# XephConnect_v0_1.net
KiCad netlist of a schematic drawn in EAGLE
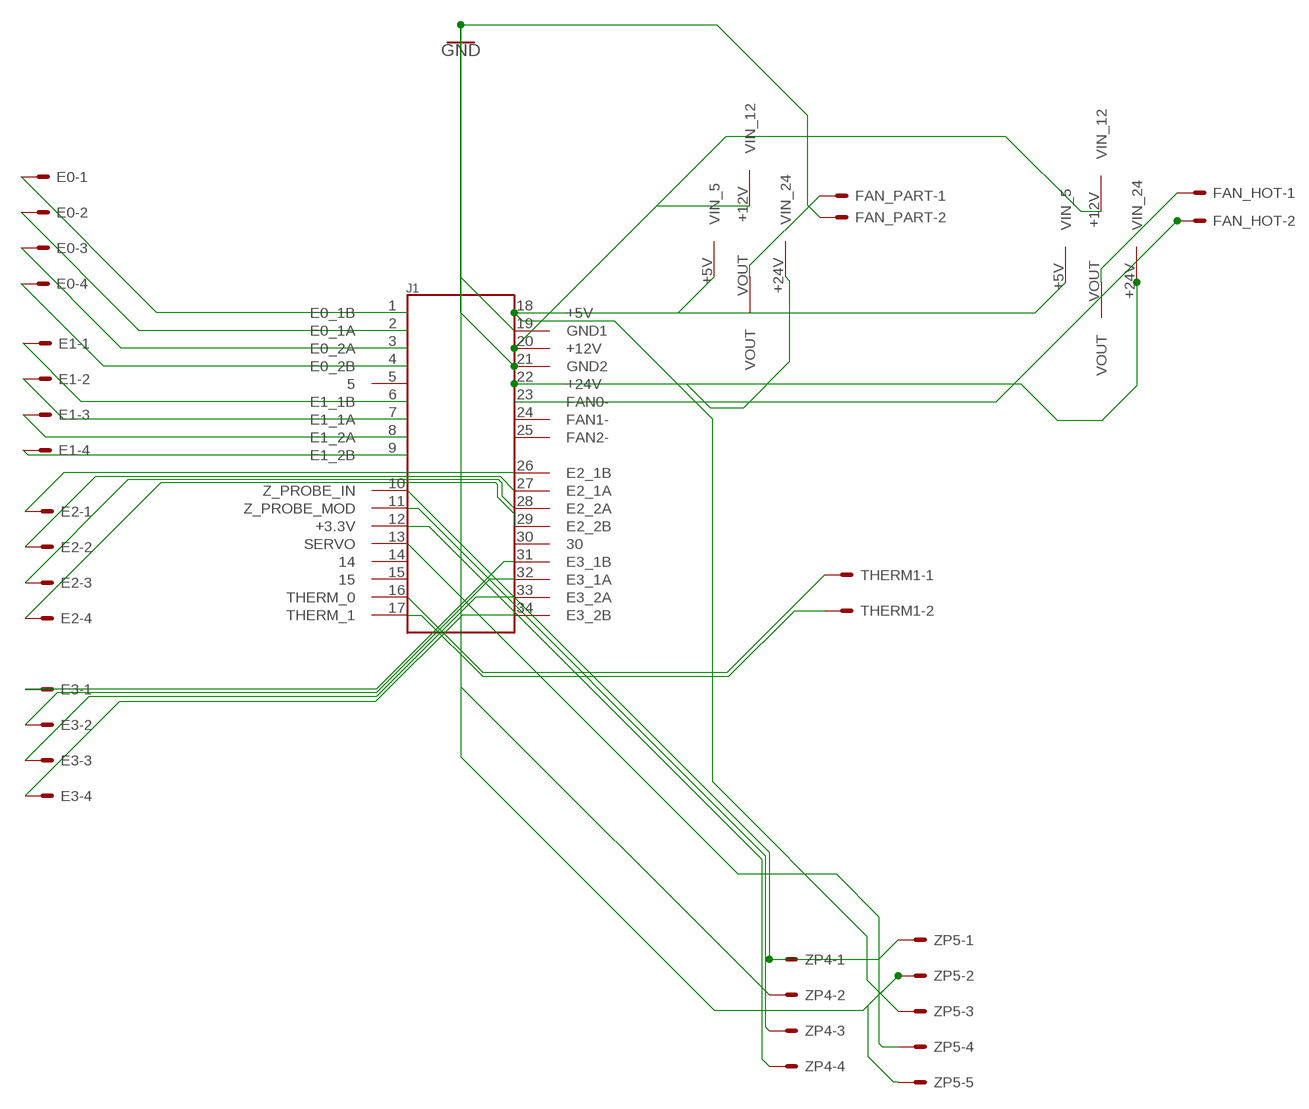
[diagram p0: schematic, sheet 1]

(export (version "E")
  (design (tool "Eeschema 10.0.6"))
  (components
    (comp (ref "E0")
      (value "22-27-2041-04")
      (footprint "eagle-import:6410-04")
      (fields (field (name "MF") "MOLEX"))
      (libsource (lib "eagle-import") (part "22-?-0427-2041"))
    )
    (comp (ref "E1")
      (value "22-27-2041-04")
      (footprint "eagle-import:6410-04")
      (fields (field (name "MF") "MOLEX"))
      (libsource (lib "eagle-import") (part "22-?-0427-2041"))
    )
    (comp (ref "E2")
      (value "22-27-2041-04")
      (footprint "eagle-import:6410-04")
      (fields (field (name "MF") "MOLEX"))
      (libsource (lib "eagle-import") (part "22-?-0427-2041"))
    )
    (comp (ref "E3")
      (value "22-27-2041-04")
      (footprint "eagle-import:6410-04")
      (fields (field (name "MF") "MOLEX"))
      (libsource (lib "eagle-import") (part "22-?-0427-2041"))
    )
    (comp (ref "FAN_HOT")
      (value "22-27-2021-02")
      (footprint "eagle-import:6410-02")
      (fields (field (name "MF") "MOLEX"))
      (libsource (lib "eagle-import") (part "22-?-0227-2021"))
    )
    (comp (ref "FAN_PART")
      (value "22-27-2021-02")
      (footprint "eagle-import:6410-02")
      (fields (field (name "MF") "MOLEX"))
      (libsource (lib "eagle-import") (part "22-?-0227-2021"))
    )
    (comp (ref "J1")
      (value "6437288-1")
      (footprint "eagle-import:TE_6437288-1")
      (fields (field (name "DIGI-KEY_PART_NUMBER") "A124384-ND") (field (name "MF") "TE Connectivity"))
      (libsource (lib "eagle-import") (part "6437288-1"))
    )
    (comp (ref "THERM1")
      (value "22-27-2021-02")
      (footprint "eagle-import:6410-02")
      (fields (field (name "MF") "MOLEX"))
      (libsource (lib "eagle-import") (part "22-?-0227-2021"))
    )
    (comp (ref "U$1")
      (value "CONN_03+01(T)")
      (footprint "eagle-import:1X03X01")
      (libsource (lib "eagle-import") (part "CONN_03+01(T)"))
    )
    (comp (ref "U$2")
      (value "CONN_03+01(T)")
      (footprint "eagle-import:1X03X01")
      (libsource (lib "eagle-import") (part "CONN_03+01(T)"))
    )
    (comp (ref "ZP4")
      (value "22-27-2041-04")
      (footprint "eagle-import:6410-04")
      (fields (field (name "MF") "MOLEX"))
      (libsource (lib "eagle-import") (part "22-?-0427-2041"))
    )
    (comp (ref "ZP5")
      (value "22-27-2051-05")
      (footprint "eagle-import:6410-05")
      (fields (field (name "MF") "MOLEX"))
      (libsource (lib "eagle-import") (part "22-?-0527-2051"))
    )
  )
  (nets
    (net (code "1") (name "/FAN1-") (class "Default")
      (node (ref "J1") (pin "24") (pinfunction "FAN1-_24") (pintype "power_in"))
    )
    (net (code "2") (name "/FAN2-") (class "Default")
      (node (ref "J1") (pin "25") (pinfunction "FAN2-_25") (pintype "power_in"))
    )
    (net (code "3") (name "GND") (class "Default")
      (node (ref "FAN_PART") (pin "2") (pinfunction "S_2") (pintype "passive"))
      (node (ref "J1") (pin "19") (pinfunction "GND1_19") (pintype "power_in"))
      (node (ref "J1") (pin "21") (pinfunction "GND2_21") (pintype "power_in"))
      (node (ref "ZP4") (pin "2") (pinfunction "S_2") (pintype "passive"))
      (node (ref "ZP5") (pin "2") (pinfunction "S_2") (pintype "passive"))
      (node (ref "ZP5") (pin "5") (pinfunction "S_5") (pintype "passive"))
    )
    (net (code "4") (name "Net-(E0A-S)") (class "Default")
      (node (ref "E0") (pin "1") (pinfunction "S_1") (pintype "passive"))
      (node (ref "J1") (pin "1") (pinfunction "E0_1B_1") (pintype "bidirectional"))
    )
    (net (code "5") (name "Net-(E0B-S)") (class "Default")
      (node (ref "E0") (pin "2") (pinfunction "S_2") (pintype "passive"))
      (node (ref "J1") (pin "2") (pinfunction "E0_1A_2") (pintype "bidirectional"))
    )
    (net (code "6") (name "Net-(E0C-S)") (class "Default")
      (node (ref "E0") (pin "3") (pinfunction "S_3") (pintype "passive"))
      (node (ref "J1") (pin "3") (pinfunction "E0_2A_3") (pintype "bidirectional"))
    )
    (net (code "7") (name "Net-(E0D-S)") (class "Default")
      (node (ref "E0") (pin "4") (pinfunction "S_4") (pintype "passive"))
      (node (ref "J1") (pin "4") (pinfunction "E0_2B_4") (pintype "bidirectional"))
    )
    (net (code "8") (name "Net-(E1A-S)") (class "Default")
      (node (ref "E1") (pin "1") (pinfunction "S_1") (pintype "passive"))
      (node (ref "J1") (pin "6") (pinfunction "E1_1B_6") (pintype "bidirectional"))
    )
    (net (code "9") (name "Net-(E1B-S)") (class "Default")
      (node (ref "E1") (pin "2") (pinfunction "S_2") (pintype "passive"))
      (node (ref "J1") (pin "7") (pinfunction "E1_1A_7") (pintype "bidirectional"))
    )
    (net (code "10") (name "Net-(E1C-S)") (class "Default")
      (node (ref "E1") (pin "3") (pinfunction "S_3") (pintype "passive"))
      (node (ref "J1") (pin "8") (pinfunction "E1_2A_8") (pintype "bidirectional"))
    )
    (net (code "11") (name "Net-(E1D-S)") (class "Default")
      (node (ref "E1") (pin "4") (pinfunction "S_4") (pintype "passive"))
      (node (ref "J1") (pin "9") (pinfunction "E1_2B_9") (pintype "bidirectional"))
    )
    (net (code "12") (name "Net-(E2A-S)") (class "Default")
      (node (ref "E2") (pin "1") (pinfunction "S_1") (pintype "passive"))
      (node (ref "J1") (pin "26") (pinfunction "E2_1B_26") (pintype "bidirectional"))
    )
    (net (code "13") (name "Net-(E2B-S)") (class "Default")
      (node (ref "E2") (pin "2") (pinfunction "S_2") (pintype "passive"))
      (node (ref "J1") (pin "27") (pinfunction "E2_1A_27") (pintype "bidirectional"))
    )
    (net (code "14") (name "Net-(E2C-S)") (class "Default")
      (node (ref "E2") (pin "3") (pinfunction "S_3") (pintype "passive"))
      (node (ref "J1") (pin "28") (pinfunction "E2_2A_28") (pintype "bidirectional"))
    )
    (net (code "15") (name "Net-(E2D-S)") (class "Default")
      (node (ref "E2") (pin "4") (pinfunction "S_4") (pintype "passive"))
      (node (ref "J1") (pin "29") (pinfunction "E2_2B_29") (pintype "bidirectional"))
    )
    (net (code "16") (name "Net-(E3A-S)") (class "Default")
      (node (ref "E3") (pin "1") (pinfunction "S_1") (pintype "passive"))
      (node (ref "J1") (pin "31") (pinfunction "E3_1B_31") (pintype "bidirectional"))
    )
    (net (code "17") (name "Net-(E3B-S)") (class "Default")
      (node (ref "E3") (pin "2") (pinfunction "S_2") (pintype "passive"))
      (node (ref "J1") (pin "32") (pinfunction "E3_1A_32") (pintype "bidirectional"))
    )
    (net (code "18") (name "Net-(E3C-S)") (class "Default")
      (node (ref "E3") (pin "3") (pinfunction "S_3") (pintype "passive"))
      (node (ref "J1") (pin "33") (pinfunction "E3_2A_33") (pintype "bidirectional"))
    )
    (net (code "19") (name "Net-(E3D-S)") (class "Default")
      (node (ref "E3") (pin "4") (pinfunction "S_4") (pintype "passive"))
      (node (ref "J1") (pin "34") (pinfunction "E3_2B_34") (pintype "bidirectional"))
    )
    (net (code "20") (name "Net-(FAN_HOTA-S)") (class "Default")
      (node (ref "FAN_HOT") (pin "1") (pinfunction "S_1") (pintype "passive"))
      (node (ref "U$2") (pin "VOUT") (pinfunction "VOUT_VOUT") (pintype "power_in"))
    )
    (net (code "21") (name "Net-(FAN_HOTB-S)") (class "Default")
      (node (ref "FAN_HOT") (pin "2") (pinfunction "S_2") (pintype "passive"))
      (node (ref "J1") (pin "23") (pinfunction "FAN0-_23") (pintype "power_in"))
    )
    (net (code "22") (name "Net-(FAN_PARTA-S)") (class "Default")
      (node (ref "FAN_PART") (pin "1") (pinfunction "S_1") (pintype "passive"))
      (node (ref "U$1") (pin "VOUT") (pinfunction "VOUT_VOUT") (pintype "power_in"))
    )
    (net (code "23") (name "Net-(J1-+3.3V)") (class "Default")
      (node (ref "J1") (pin "12") (pinfunction "+3.3V_12") (pintype "power_in"))
      (node (ref "ZP4") (pin "4") (pinfunction "S_4") (pintype "passive"))
    )
    (net (code "24") (name "Net-(J1-+5V)") (class "Default")
      (node (ref "J1") (pin "18") (pinfunction "+5V_18") (pintype "power_in"))
      (node (ref "U$1") (pin "+5V") (pinfunction "VIN_5_+5V") (pintype "power_in"))
      (node (ref "U$2") (pin "+5V") (pinfunction "VIN_5_+5V") (pintype "power_in"))
      (node (ref "ZP5") (pin "3") (pinfunction "S_3") (pintype "passive"))
    )
    (net (code "25") (name "Net-(J1-+12V)") (class "Default")
      (node (ref "J1") (pin "20") (pinfunction "+12V_20") (pintype "power_in"))
      (node (ref "U$1") (pin "+12V") (pinfunction "VIN_12_+12V") (pintype "power_in"))
      (node (ref "U$2") (pin "+12V") (pinfunction "VIN_12_+12V") (pintype "power_in"))
    )
    (net (code "26") (name "Net-(J1-+24V)") (class "Default")
      (node (ref "J1") (pin "22") (pinfunction "+24V_22") (pintype "power_in"))
      (node (ref "U$1") (pin "+24V") (pinfunction "VIN_24_+24V") (pintype "power_in"))
      (node (ref "U$2") (pin "+24V") (pinfunction "VIN_24_+24V") (pintype "power_in"))
    )
    (net (code "27") (name "Net-(J1-SERVO)") (class "Default")
      (node (ref "J1") (pin "13") (pinfunction "SERVO_13") (pintype "bidirectional"))
      (node (ref "ZP5") (pin "4") (pinfunction "S_4") (pintype "passive"))
    )
    (net (code "28") (name "Net-(J1-THERM_0)") (class "Default")
      (node (ref "J1") (pin "16") (pinfunction "THERM_0_16") (pintype "power_in"))
      (node (ref "THERM1") (pin "1") (pinfunction "S_1") (pintype "passive"))
    )
    (net (code "29") (name "Net-(J1-THERM_1)") (class "Default")
      (node (ref "J1") (pin "17") (pinfunction "THERM_1_17") (pintype "power_in"))
      (node (ref "THERM1") (pin "2") (pinfunction "S_2") (pintype "passive"))
    )
    (net (code "30") (name "Net-(J1-Z_PROBE_IN)") (class "Default")
      (node (ref "J1") (pin "10") (pinfunction "Z_PROBE_IN_10") (pintype "bidirectional"))
      (node (ref "ZP4") (pin "1") (pinfunction "S_1") (pintype "passive"))
      (node (ref "ZP5") (pin "1") (pinfunction "S_1") (pintype "passive"))
    )
    (net (code "31") (name "Net-(J1-Z_PROBE_MOD)") (class "Default")
      (node (ref "J1") (pin "11") (pinfunction "Z_PROBE_MOD_11") (pintype "bidirectional"))
      (node (ref "ZP4") (pin "3") (pinfunction "S_3") (pintype "passive"))
    )
    (net (code "32") (name "unconnected-(J1-Pad5)") (class "Default")
      (node (ref "J1") (pin "5") (pinfunction "5_5") (pintype "no_connect"))
    )
    (net (code "33") (name "unconnected-(J1-Pad14)") (class "Default")
      (node (ref "J1") (pin "14") (pinfunction "14_14") (pintype "no_connect"))
    )
    (net (code "34") (name "unconnected-(J1-Pad15)") (class "Default")
      (node (ref "J1") (pin "15") (pinfunction "15_15") (pintype "no_connect"))
    )
    (net (code "35") (name "unconnected-(J1-Pad30)") (class "Default")
      (node (ref "J1") (pin "30") (pinfunction "30_30") (pintype "no_connect"))
    )
  )
)
